# Holoboard_power_supply.net
KiCad netlist of a schematic drawn in Altium Designer
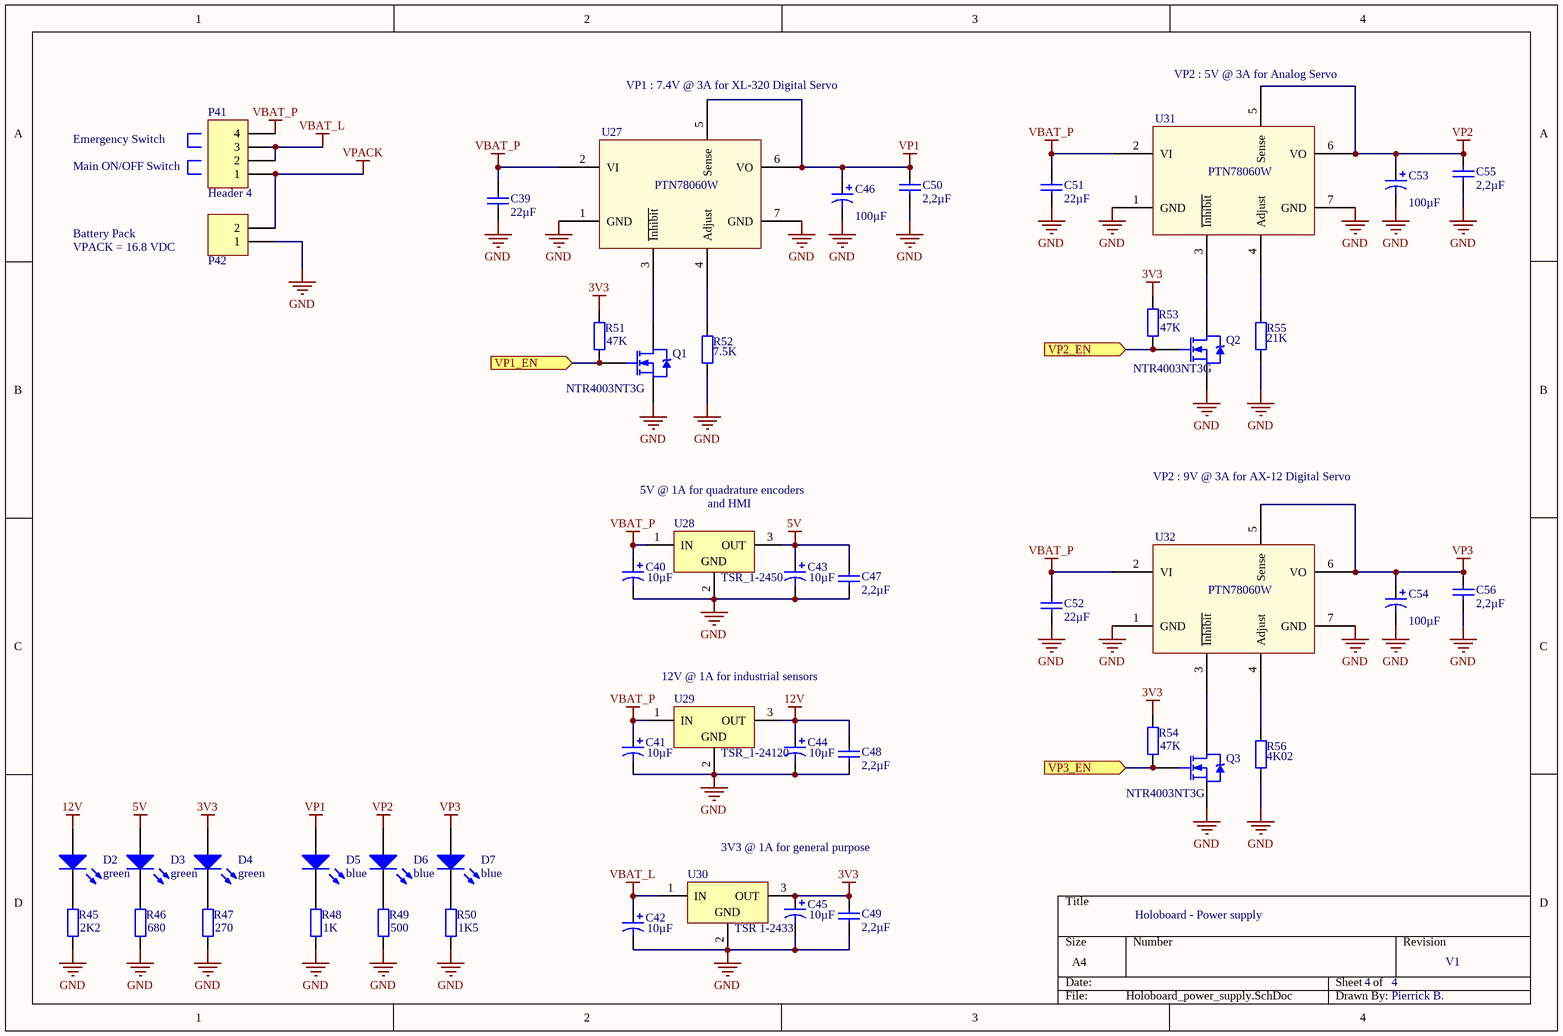
[diagram p0: Holoboard_power_supply.SchDoc]

(export (version "E")
  (design (tool "Eeschema 10.0.6"))
  (components
    (comp (ref "C39")
      (value "22µF")
      (footprint "Boitier tantale B")
      (description "Capacitor")
      (fields (field (name "Comment") "Cap") (field (name "PUBLISHER") "Altium Limited"))
      (libsource (lib "LIBRARY IGREBOT") (part "Cap"))
    )
    (comp (ref "C40")
      (value "10µF")
      (footprint "Boitier tantale B")
      (description "Polarized Capacitor")
      (fields (field (name "Comment") "Cap Pol") (field (name "PUBLISHER") "Altium Limited"))
      (libsource (lib "LIBRARY IGREBOT") (part "Cap Pol"))
    )
    (comp (ref "C41")
      (value "10µF")
      (footprint "Boitier tantale B")
      (description "Polarized Capacitor")
      (fields (field (name "Comment") "Cap Pol") (field (name "PUBLISHER") "Altium Limited"))
      (libsource (lib "LIBRARY IGREBOT") (part "Cap Pol"))
    )
    (comp (ref "C42")
      (value "10µF")
      (footprint "Boitier tantale B")
      (description "Polarized Capacitor")
      (fields (field (name "Comment") "Cap Pol") (field (name "PUBLISHER") "Altium Limited"))
      (libsource (lib "LIBRARY IGREBOT") (part "Cap Pol"))
    )
    (comp (ref "C43")
      (value "10µF")
      (footprint "Boitier tantale B")
      (description "Polarized Capacitor")
      (fields (field (name "Comment") "Cap Pol") (field (name "PUBLISHER") "Altium Limited"))
      (libsource (lib "LIBRARY IGREBOT") (part "Cap Pol"))
    )
    (comp (ref "C44")
      (value "10µF")
      (footprint "Boitier tantale B")
      (description "Polarized Capacitor")
      (fields (field (name "Comment") "Cap Pol") (field (name "PUBLISHER") "Altium Limited"))
      (libsource (lib "LIBRARY IGREBOT") (part "Cap Pol"))
    )
    (comp (ref "C45")
      (value "10µF")
      (footprint "Boitier tantale B")
      (description "Polarized Capacitor")
      (fields (field (name "Comment") "Cap Pol") (field (name "PUBLISHER") "Altium Limited"))
      (libsource (lib "LIBRARY IGREBOT") (part "Cap Pol"))
    )
    (comp (ref "C46")
      (value "100µF")
      (footprint "Boitier tantale C")
      (description "Polarized Capacitor")
      (fields (field (name "Comment") "Cap Pol") (field (name "PUBLISHER") "Altium Limited"))
      (libsource (lib "LIBRARY IGREBOT") (part "Cap Pol"))
    )
    (comp (ref "C47")
      (value "2,2µF")
      (footprint "C0805")
      (description "Capacitor")
      (fields (field (name "Comment") "Cap") (field (name "PUBLISHER") "Altium Limited"))
      (libsource (lib "LIBRARY IGREBOT") (part "Cap"))
    )
    (comp (ref "C48")
      (value "2,2µF")
      (footprint "C0805")
      (description "Capacitor")
      (fields (field (name "Comment") "Cap") (field (name "PUBLISHER") "Altium Limited"))
      (libsource (lib "LIBRARY IGREBOT") (part "Cap"))
    )
    (comp (ref "C49")
      (value "2,2µF")
      (footprint "C0805")
      (description "Capacitor")
      (fields (field (name "Comment") "Cap") (field (name "PUBLISHER") "Altium Limited"))
      (libsource (lib "LIBRARY IGREBOT") (part "Cap"))
    )
    (comp (ref "C50")
      (value "2,2µF")
      (footprint "C0805")
      (description "Capacitor")
      (fields (field (name "Comment") "Cap") (field (name "PUBLISHER") "Altium Limited"))
      (libsource (lib "LIBRARY IGREBOT") (part "Cap"))
    )
    (comp (ref "C51")
      (value "22µF")
      (footprint "Boitier tantale B")
      (description "Capacitor")
      (fields (field (name "Comment") "Cap") (field (name "PUBLISHER") "Altium Limited"))
      (libsource (lib "LIBRARY IGREBOT") (part "Cap"))
    )
    (comp (ref "C52")
      (value "22µF")
      (footprint "Boitier tantale B")
      (description "Capacitor")
      (fields (field (name "Comment") "Cap") (field (name "PUBLISHER") "Altium Limited"))
      (libsource (lib "LIBRARY IGREBOT") (part "Cap"))
    )
    (comp (ref "C53")
      (value "100µF")
      (footprint "Boitier tantale C")
      (description "Polarized Capacitor")
      (fields (field (name "Comment") "Cap Pol") (field (name "PUBLISHER") "Altium Limited"))
      (libsource (lib "LIBRARY IGREBOT") (part "Cap Pol"))
    )
    (comp (ref "C54")
      (value "100µF")
      (footprint "Boitier tantale C")
      (description "Polarized Capacitor")
      (fields (field (name "Comment") "Cap Pol") (field (name "PUBLISHER") "Altium Limited"))
      (libsource (lib "LIBRARY IGREBOT") (part "Cap Pol"))
    )
    (comp (ref "C55")
      (value "2,2µF")
      (footprint "C0805")
      (description "Capacitor")
      (fields (field (name "Comment") "Cap") (field (name "PUBLISHER") "Altium Limited"))
      (libsource (lib "LIBRARY IGREBOT") (part "Cap"))
    )
    (comp (ref "C56")
      (value "2,2µF")
      (footprint "C0805")
      (description "Capacitor")
      (fields (field (name "Comment") "Cap") (field (name "PUBLISHER") "Altium Limited"))
      (libsource (lib "LIBRARY IGREBOT") (part "Cap"))
    )
    (comp (ref "D2")
      (value "green")
      (footprint "KP-2012")
      (description "Typical RED GaAs LED")
      (fields (field (name "PUBLISHER") "Altium Limited"))
      (libsource (lib "LIBRARY IGREBOT") (part "LED1"))
    )
    (comp (ref "D3")
      (value "green")
      (footprint "KP-2012")
      (description "Typical RED GaAs LED")
      (fields (field (name "PUBLISHER") "Altium Limited"))
      (libsource (lib "LIBRARY IGREBOT") (part "LED1"))
    )
    (comp (ref "D4")
      (value "green")
      (footprint "KP-2012")
      (description "Typical RED GaAs LED")
      (fields (field (name "PUBLISHER") "Altium Limited"))
      (libsource (lib "LIBRARY IGREBOT") (part "LED1"))
    )
    (comp (ref "D5")
      (value "blue")
      (footprint "KP-2012")
      (description "Typical RED GaAs LED")
      (fields (field (name "PUBLISHER") "Altium Limited"))
      (libsource (lib "LIBRARY IGREBOT") (part "LED1"))
    )
    (comp (ref "D6")
      (value "blue")
      (footprint "KP-2012")
      (description "Typical RED GaAs LED")
      (fields (field (name "PUBLISHER") "Altium Limited"))
      (libsource (lib "LIBRARY IGREBOT") (part "LED1"))
    )
    (comp (ref "D7")
      (value "blue")
      (footprint "KP-2012")
      (description "Typical RED GaAs LED")
      (fields (field (name "PUBLISHER") "Altium Limited"))
      (libsource (lib "LIBRARY IGREBOT") (part "LED1"))
    )
    (comp (ref "P41")
      (value "Header 4")
      (footprint "IMO - 20.155MH/4")
      (description "Header, 4-Pin")
      (fields (field (name "PUBLISHER") "Altium Limited"))
      (libsource (lib "LIBRARY IGREBOT") (part "Header 4"))
    )
    (comp (ref "P42")
      (value "Header 2")
      (footprint "IMO - 20.155MH/2")
      (description "Header, 2-Pin")
      (fields (field (name "PUBLISHER") "Altium Limited"))
      (libsource (lib "LIBRARY IGREBOT") (part "Header 2"))
    )
    (comp (ref "Q1")
      (value "NTR4003NT3G")
      (footprint "SOT-23")
      (description "N-Channel Power MOSFET")
      (fields (field (name "PUBLISHER") "Altium Limited"))
      (libsource (lib "LIBRARY IGREBOT") (part "NMOS-2"))
    )
    (comp (ref "Q2")
      (value "NTR4003NT3G")
      (footprint "SOT-23")
      (description "N-Channel Power MOSFET")
      (fields (field (name "PUBLISHER") "Altium Limited"))
      (libsource (lib "LIBRARY IGREBOT") (part "NMOS-2"))
    )
    (comp (ref "Q3")
      (value "NTR4003NT3G")
      (footprint "SOT-23")
      (description "N-Channel Power MOSFET")
      (fields (field (name "PUBLISHER") "Altium Limited"))
      (libsource (lib "LIBRARY IGREBOT") (part "NMOS-2"))
    )
    (comp (ref "R45")
      (value "2K2")
      (footprint "0603")
      (description "Resistor")
      (fields (field (name "Comment") "Res2") (field (name "PUBLISHER") "Altium Limited"))
      (libsource (lib "LIBRARY IGREBOT") (part "Res2"))
    )
    (comp (ref "R46")
      (value "680")
      (footprint "0603")
      (description "Resistor")
      (fields (field (name "Comment") "Res2") (field (name "PUBLISHER") "Altium Limited"))
      (libsource (lib "LIBRARY IGREBOT") (part "Res2"))
    )
    (comp (ref "R47")
      (value "270")
      (footprint "0603")
      (description "Resistor")
      (fields (field (name "Comment") "Res2") (field (name "PUBLISHER") "Altium Limited"))
      (libsource (lib "LIBRARY IGREBOT") (part "Res2"))
    )
    (comp (ref "R48")
      (value "1K")
      (footprint "0603")
      (description "Resistor")
      (fields (field (name "Comment") "Res2") (field (name "PUBLISHER") "Altium Limited"))
      (libsource (lib "LIBRARY IGREBOT") (part "Res2"))
    )
    (comp (ref "R49")
      (value "500")
      (footprint "0603")
      (description "Resistor")
      (fields (field (name "Comment") "Res2") (field (name "PUBLISHER") "Altium Limited"))
      (libsource (lib "LIBRARY IGREBOT") (part "Res2"))
    )
    (comp (ref "R50")
      (value "1K5")
      (footprint "0603")
      (description "Resistor")
      (fields (field (name "Comment") "Res2") (field (name "PUBLISHER") "Altium Limited"))
      (libsource (lib "LIBRARY IGREBOT") (part "Res2"))
    )
    (comp (ref "R51")
      (value "47K")
      (footprint "0603")
      (description "Resistor")
      (fields (field (name "Comment") "Res2") (field (name "PUBLISHER") "Altium Limited"))
      (libsource (lib "LIBRARY IGREBOT") (part "Res2"))
    )
    (comp (ref "R52")
      (value "7.5K")
      (footprint "0603")
      (description "Resistor")
      (fields (field (name "Comment") "Res2") (field (name "PUBLISHER") "Altium Limited"))
      (libsource (lib "LIBRARY IGREBOT") (part "Res2"))
    )
    (comp (ref "R53")
      (value "47K")
      (footprint "0603")
      (description "Resistor")
      (fields (field (name "Comment") "Res2") (field (name "PUBLISHER") "Altium Limited"))
      (libsource (lib "LIBRARY IGREBOT") (part "Res2"))
    )
    (comp (ref "R54")
      (value "47K")
      (footprint "0603")
      (description "Resistor")
      (fields (field (name "Comment") "Res2") (field (name "PUBLISHER") "Altium Limited"))
      (libsource (lib "LIBRARY IGREBOT") (part "Res2"))
    )
    (comp (ref "R55")
      (value "21K")
      (footprint "0603")
      (description "Resistor")
      (fields (field (name "Comment") "Res2") (field (name "PUBLISHER") "Altium Limited"))
      (libsource (lib "LIBRARY IGREBOT") (part "Res2"))
    )
    (comp (ref "R56")
      (value "4K02")
      (footprint "0603")
      (description "Resistor")
      (fields (field (name "Comment") "Res2") (field (name "PUBLISHER") "Altium Limited"))
      (libsource (lib "LIBRARY IGREBOT") (part "Res2"))
    )
    (comp (ref "U27")
      (value "PTN78060W")
      (footprint "EUW")
      (libsource (lib "LIBRARY IGREBOT") (part "PTN78060W"))
    )
    (comp (ref "U28")
      (value "TSR_1-2450")
      (footprint "TSR-1")
      (libsource (lib "LIBRARY IGREBOT") (part "TSR_1-2450"))
    )
    (comp (ref "U29")
      (value "TSR_1-24120")
      (footprint "TSR-1")
      (libsource (lib "LIBRARY IGREBOT") (part "TSR_1-24120"))
    )
    (comp (ref "U30")
      (value "TSR 1-2433")
      (footprint "TSR-1")
      (libsource (lib "LIBRARY IGREBOT") (part "TSR 1-2433"))
    )
    (comp (ref "U31")
      (value "PTN78060W")
      (footprint "EUW")
      (libsource (lib "LIBRARY IGREBOT") (part "PTN78060W"))
    )
    (comp (ref "U32")
      (value "PTN78060W")
      (footprint "EUW")
      (libsource (lib "LIBRARY IGREBOT") (part "PTN78060W"))
    )
  )
  (nets
    (net (code "1") (name "/VP1_EN") (class "Default")
      (node (ref "Q1") (pin "1") (pinfunction "G_1") (pintype "passive"))
      (node (ref "R51") (pin "1") (pinfunction "1_1") (pintype "passive"))
    )
    (net (code "2") (name "/VP2_EN") (class "Default")
      (node (ref "Q2") (pin "1") (pinfunction "G_1") (pintype "passive"))
      (node (ref "R53") (pin "1") (pinfunction "1_1") (pintype "passive"))
    )
    (net (code "3") (name "/VP3_EN") (class "Default")
      (node (ref "Q3") (pin "1") (pinfunction "G_1") (pintype "passive"))
      (node (ref "R54") (pin "1") (pinfunction "1_1") (pintype "passive"))
    )
    (net (code "4") (name "3V3") (class "Default")
      (node (ref "C45") (pin "1") (pinfunction "1_1") (pintype "passive"))
      (node (ref "C49") (pin "2") (pinfunction "2_2") (pintype "passive"))
      (node (ref "D4") (pin "1") (pinfunction "A_1") (pintype "passive"))
      (node (ref "R51") (pin "2") (pinfunction "2_2") (pintype "passive"))
      (node (ref "R53") (pin "2") (pinfunction "2_2") (pintype "passive"))
      (node (ref "R54") (pin "2") (pinfunction "2_2") (pintype "passive"))
      (node (ref "U30") (pin "3") (pinfunction "OUT_3") (pintype "power_in"))
    )
    (net (code "5") (name "5V") (class "Default")
      (node (ref "C43") (pin "1") (pinfunction "1_1") (pintype "passive"))
      (node (ref "C47") (pin "2") (pinfunction "2_2") (pintype "passive"))
      (node (ref "D3") (pin "1") (pinfunction "A_1") (pintype "passive"))
      (node (ref "U28") (pin "3") (pinfunction "OUT_3") (pintype "power_in"))
    )
    (net (code "6") (name "12V") (class "Default")
      (node (ref "C44") (pin "1") (pinfunction "1_1") (pintype "passive"))
      (node (ref "C48") (pin "2") (pinfunction "2_2") (pintype "passive"))
      (node (ref "D2") (pin "1") (pinfunction "A_1") (pintype "passive"))
      (node (ref "U29") (pin "3") (pinfunction "OUT_3") (pintype "power_in"))
    )
    (net (code "7") (name "GND") (class "Default")
      (node (ref "C39") (pin "1") (pinfunction "1_1") (pintype "passive"))
      (node (ref "C40") (pin "2") (pinfunction "2_2") (pintype "passive"))
      (node (ref "C41") (pin "2") (pinfunction "2_2") (pintype "passive"))
      (node (ref "C42") (pin "2") (pinfunction "2_2") (pintype "passive"))
      (node (ref "C43") (pin "2") (pinfunction "2_2") (pintype "passive"))
      (node (ref "C44") (pin "2") (pinfunction "2_2") (pintype "passive"))
      (node (ref "C45") (pin "2") (pinfunction "2_2") (pintype "passive"))
      (node (ref "C46") (pin "2") (pinfunction "2_2") (pintype "passive"))
      (node (ref "C47") (pin "1") (pinfunction "1_1") (pintype "passive"))
      (node (ref "C48") (pin "1") (pinfunction "1_1") (pintype "passive"))
      (node (ref "C49") (pin "1") (pinfunction "1_1") (pintype "passive"))
      (node (ref "C50") (pin "1") (pinfunction "1_1") (pintype "passive"))
      (node (ref "C51") (pin "1") (pinfunction "1_1") (pintype "passive"))
      (node (ref "C52") (pin "1") (pinfunction "1_1") (pintype "passive"))
      (node (ref "C53") (pin "2") (pinfunction "2_2") (pintype "passive"))
      (node (ref "C54") (pin "2") (pinfunction "2_2") (pintype "passive"))
      (node (ref "C55") (pin "1") (pinfunction "1_1") (pintype "passive"))
      (node (ref "C56") (pin "1") (pinfunction "1_1") (pintype "passive"))
      (node (ref "P42") (pin "1") (pinfunction "1_1") (pintype "passive"))
      (node (ref "Q1") (pin "2") (pinfunction "S_2") (pintype "passive"))
      (node (ref "Q2") (pin "2") (pinfunction "S_2") (pintype "passive"))
      (node (ref "Q3") (pin "2") (pinfunction "S_2") (pintype "passive"))
      (node (ref "R45") (pin "1") (pinfunction "1_1") (pintype "passive"))
      (node (ref "R46") (pin "1") (pinfunction "1_1") (pintype "passive"))
      (node (ref "R47") (pin "1") (pinfunction "1_1") (pintype "passive"))
      (node (ref "R48") (pin "1") (pinfunction "1_1") (pintype "passive"))
      (node (ref "R49") (pin "1") (pinfunction "1_1") (pintype "passive"))
      (node (ref "R50") (pin "1") (pinfunction "1_1") (pintype "passive"))
      (node (ref "R52") (pin "1") (pinfunction "1_1") (pintype "passive"))
      (node (ref "R55") (pin "1") (pinfunction "1_1") (pintype "passive"))
      (node (ref "R56") (pin "1") (pinfunction "1_1") (pintype "passive"))
      (node (ref "U27") (pin "1") (pinfunction "GND_1") (pintype "power_in"))
      (node (ref "U27") (pin "7") (pinfunction "GND_7") (pintype "power_in"))
      (node (ref "U28") (pin "2") (pinfunction "GND_2") (pintype "power_in"))
      (node (ref "U29") (pin "2") (pinfunction "GND_2") (pintype "power_in"))
      (node (ref "U30") (pin "2") (pinfunction "GND_2") (pintype "power_in"))
      (node (ref "U31") (pin "1") (pinfunction "GND_1") (pintype "power_in"))
      (node (ref "U31") (pin "7") (pinfunction "GND_7") (pintype "power_in"))
      (node (ref "U32") (pin "1") (pinfunction "GND_1") (pintype "power_in"))
      (node (ref "U32") (pin "7") (pinfunction "GND_7") (pintype "power_in"))
    )
    (net (code "8") (name "Net-(D2-K)") (class "Default")
      (node (ref "D2") (pin "2") (pinfunction "K_2") (pintype "passive"))
      (node (ref "R45") (pin "2") (pinfunction "2_2") (pintype "passive"))
    )
    (net (code "9") (name "Net-(D3-K)") (class "Default")
      (node (ref "D3") (pin "2") (pinfunction "K_2") (pintype "passive"))
      (node (ref "R46") (pin "2") (pinfunction "2_2") (pintype "passive"))
    )
    (net (code "10") (name "Net-(D4-K)") (class "Default")
      (node (ref "D4") (pin "2") (pinfunction "K_2") (pintype "passive"))
      (node (ref "R47") (pin "2") (pinfunction "2_2") (pintype "passive"))
    )
    (net (code "11") (name "Net-(D5-K)") (class "Default")
      (node (ref "D5") (pin "2") (pinfunction "K_2") (pintype "passive"))
      (node (ref "R48") (pin "2") (pinfunction "2_2") (pintype "passive"))
    )
    (net (code "12") (name "Net-(D6-K)") (class "Default")
      (node (ref "D6") (pin "2") (pinfunction "K_2") (pintype "passive"))
      (node (ref "R49") (pin "2") (pinfunction "2_2") (pintype "passive"))
    )
    (net (code "13") (name "Net-(D7-K)") (class "Default")
      (node (ref "D7") (pin "2") (pinfunction "K_2") (pintype "passive"))
      (node (ref "R50") (pin "2") (pinfunction "2_2") (pintype "passive"))
    )
    (net (code "14") (name "Net-(Q1-D)") (class "Default")
      (node (ref "Q1") (pin "3") (pinfunction "D_3") (pintype "passive"))
      (node (ref "U27") (pin "3") (pinfunction "~{Inhibit}_3") (pintype "power_in"))
    )
    (net (code "15") (name "Net-(Q2-D)") (class "Default")
      (node (ref "Q2") (pin "3") (pinfunction "D_3") (pintype "passive"))
      (node (ref "U31") (pin "3") (pinfunction "~{Inhibit}_3") (pintype "power_in"))
    )
    (net (code "16") (name "Net-(Q3-D)") (class "Default")
      (node (ref "Q3") (pin "3") (pinfunction "D_3") (pintype "passive"))
      (node (ref "U32") (pin "3") (pinfunction "~{Inhibit}_3") (pintype "power_in"))
    )
    (net (code "17") (name "Net-(U27-Adjust)") (class "Default")
      (node (ref "R52") (pin "2") (pinfunction "2_2") (pintype "passive"))
      (node (ref "U27") (pin "4") (pinfunction "Adjust_4") (pintype "power_in"))
    )
    (net (code "18") (name "Net-(U31-Adjust)") (class "Default")
      (node (ref "R55") (pin "2") (pinfunction "2_2") (pintype "passive"))
      (node (ref "U31") (pin "4") (pinfunction "Adjust_4") (pintype "power_in"))
    )
    (net (code "19") (name "Net-(U32-Adjust)") (class "Default")
      (node (ref "R56") (pin "2") (pinfunction "2_2") (pintype "passive"))
      (node (ref "U32") (pin "4") (pinfunction "Adjust_4") (pintype "power_in"))
    )
    (net (code "20") (name "VBAT_L") (class "Default")
      (node (ref "C42") (pin "1") (pinfunction "1_1") (pintype "passive"))
      (node (ref "P41") (pin "2") (pinfunction "2_2") (pintype "passive"))
      (node (ref "P41") (pin "3") (pinfunction "3_3") (pintype "passive"))
      (node (ref "U30") (pin "1") (pinfunction "IN_1") (pintype "power_in"))
    )
    (net (code "21") (name "VBAT_P") (class "Default")
      (node (ref "C39") (pin "2") (pinfunction "2_2") (pintype "passive"))
      (node (ref "C40") (pin "1") (pinfunction "1_1") (pintype "passive"))
      (node (ref "C41") (pin "1") (pinfunction "1_1") (pintype "passive"))
      (node (ref "C51") (pin "2") (pinfunction "2_2") (pintype "passive"))
      (node (ref "C52") (pin "2") (pinfunction "2_2") (pintype "passive"))
      (node (ref "P41") (pin "4") (pinfunction "4_4") (pintype "passive"))
      (node (ref "U27") (pin "2") (pinfunction "VI_2") (pintype "power_in"))
      (node (ref "U28") (pin "1") (pinfunction "IN_1") (pintype "power_in"))
      (node (ref "U29") (pin "1") (pinfunction "IN_1") (pintype "power_in"))
      (node (ref "U31") (pin "2") (pinfunction "VI_2") (pintype "power_in"))
      (node (ref "U32") (pin "2") (pinfunction "VI_2") (pintype "power_in"))
    )
    (net (code "22") (name "VP1") (class "Default")
      (node (ref "C46") (pin "1") (pinfunction "1_1") (pintype "passive"))
      (node (ref "C50") (pin "2") (pinfunction "2_2") (pintype "passive"))
      (node (ref "D5") (pin "1") (pinfunction "A_1") (pintype "passive"))
      (node (ref "U27") (pin "5") (pinfunction "Sense_5") (pintype "power_in"))
      (node (ref "U27") (pin "6") (pinfunction "VO_6") (pintype "power_in"))
    )
    (net (code "23") (name "VP2") (class "Default")
      (node (ref "C53") (pin "1") (pinfunction "1_1") (pintype "passive"))
      (node (ref "C55") (pin "2") (pinfunction "2_2") (pintype "passive"))
      (node (ref "D6") (pin "1") (pinfunction "A_1") (pintype "passive"))
      (node (ref "U31") (pin "5") (pinfunction "Sense_5") (pintype "power_in"))
      (node (ref "U31") (pin "6") (pinfunction "VO_6") (pintype "power_in"))
    )
    (net (code "24") (name "VP3") (class "Default")
      (node (ref "C54") (pin "1") (pinfunction "1_1") (pintype "passive"))
      (node (ref "C56") (pin "2") (pinfunction "2_2") (pintype "passive"))
      (node (ref "D7") (pin "1") (pinfunction "A_1") (pintype "passive"))
      (node (ref "U32") (pin "5") (pinfunction "Sense_5") (pintype "power_in"))
      (node (ref "U32") (pin "6") (pinfunction "VO_6") (pintype "power_in"))
    )
    (net (code "25") (name "VPACK") (class "Default")
      (node (ref "P41") (pin "1") (pinfunction "1_1") (pintype "passive"))
      (node (ref "P42") (pin "2") (pinfunction "2_2") (pintype "passive"))
    )
  )
)
